# main.net
KiCad netlist of a schematic drawn in Altium Designer
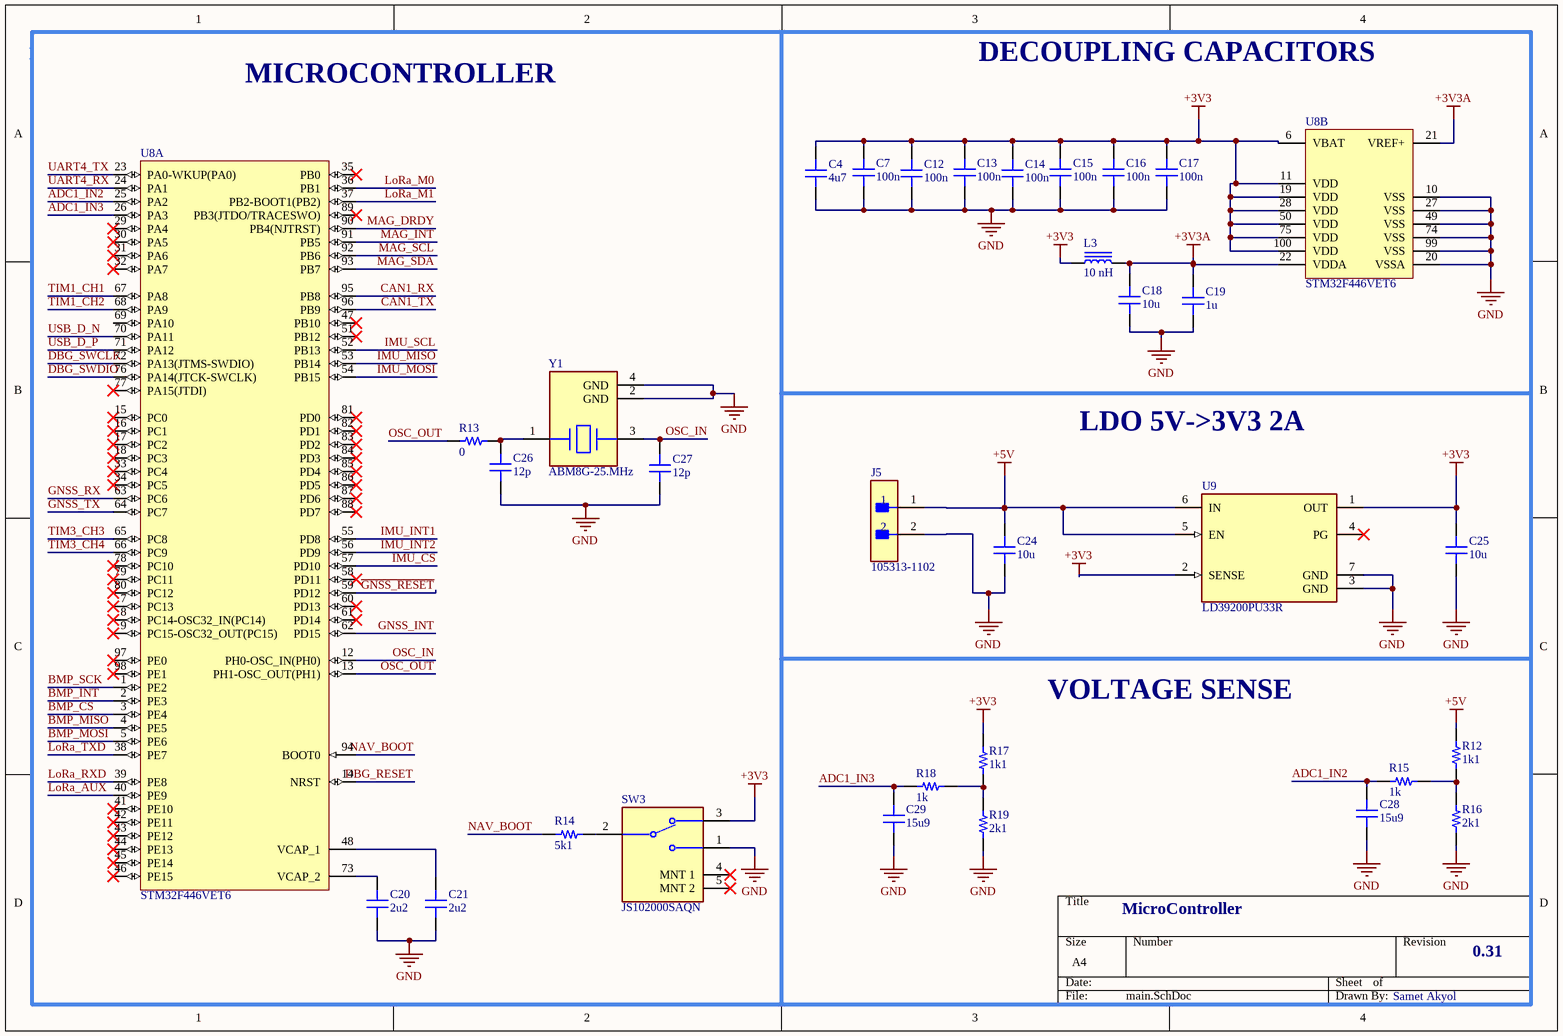
[diagram p0: main.SchDoc]

(export (version "E")
  (design (tool "Eeschema 10.0.6"))
  (components
    (comp (ref "C4")
      (value "4u7")
      (footprint "CAP 0402_1005")
      (description "CAP CER 0.1UF 10V X7R 0402")
      (fields
        (field (name "PART NUMBER") "MD0402BB104K100NGHT-EM")
        (field (name "MANUFACTURER") "Knowles Novacap")
      )
      (libsource (lib "Celestial Altium Library - altium_library") (part "Capacitor"))
    )
    (comp (ref "C7")
      (value "100n")
      (footprint "CAP 0402_1005")
      (description "CAP CER 0.1UF 10V X7R 0402")
      (fields
        (field (name "PART NUMBER") "MD0402BB104K100NGHT-EM")
        (field (name "MANUFACTURER") "Knowles Novacap")
      )
      (libsource (lib "Celestial Altium Library - altium_library") (part "Capacitor"))
    )
    (comp (ref "C12")
      (value "100n")
      (footprint "CAP 0402_1005")
      (description "CAP CER 0.1UF 10V X7R 0402")
      (fields
        (field (name "PART NUMBER") "MD0402BB104K100NGHT-EM")
        (field (name "MANUFACTURER") "Knowles Novacap")
      )
      (libsource (lib "Celestial Altium Library - altium_library") (part "Capacitor"))
    )
    (comp (ref "C13")
      (value "100n")
      (footprint "CAP 0402_1005")
      (description "CAP CER 0.1UF 10V X7R 0402")
      (fields
        (field (name "PART NUMBER") "MD0402BB104K100NGHT-EM")
        (field (name "MANUFACTURER") "Knowles Novacap")
      )
      (libsource (lib "Celestial Altium Library - altium_library") (part "Capacitor"))
    )
    (comp (ref "C14")
      (value "100n")
      (footprint "CAP 0402_1005")
      (description "CAP CER 0.1UF 10V X7R 0402")
      (fields
        (field (name "PART NUMBER") "MD0402BB104K100NGHT-EM")
        (field (name "MANUFACTURER") "Knowles Novacap")
      )
      (libsource (lib "Celestial Altium Library - altium_library") (part "Capacitor"))
    )
    (comp (ref "C15")
      (value "100n")
      (footprint "CAP 0402_1005")
      (description "CAP CER 0.1UF 10V X7R 0402")
      (fields
        (field (name "PART NUMBER") "MD0402BB104K100NGHT-EM")
        (field (name "MANUFACTURER") "Knowles Novacap")
      )
      (libsource (lib "Celestial Altium Library - altium_library") (part "Capacitor"))
    )
    (comp (ref "C16")
      (value "100n")
      (footprint "CAP 0402_1005")
      (description "CAP CER 0.1UF 10V X7R 0402")
      (fields
        (field (name "PART NUMBER") "MD0402BB104K100NGHT-EM")
        (field (name "MANUFACTURER") "Knowles Novacap")
      )
      (libsource (lib "Celestial Altium Library - altium_library") (part "Capacitor"))
    )
    (comp (ref "C17")
      (value "100n")
      (footprint "CAP 0402_1005")
      (description "CAP CER 0.1UF 10V X7R 0402")
      (fields
        (field (name "PART NUMBER") "MD0402BB104K100NGHT-EM")
        (field (name "MANUFACTURER") "Knowles Novacap")
      )
      (libsource (lib "Celestial Altium Library - altium_library") (part "Capacitor"))
    )
    (comp (ref "C18")
      (value "10u")
      (footprint "CAP 0402_1005")
      (description "CAP CER 0.1UF 10V X7R 0402")
      (fields
        (field (name "PART NUMBER") "MD0402BB104K100NGHT-EM")
        (field (name "MANUFACTURER") "Knowles Novacap")
      )
      (libsource (lib "Celestial Altium Library - altium_library") (part "Capacitor"))
    )
    (comp (ref "C19")
      (value "1u")
      (footprint "CAP 0402_1005")
      (description "CAP CER 0.1UF 10V X7R 0402")
      (fields
        (field (name "PART NUMBER") "MD0402BB104K100NGHT-EM")
        (field (name "MANUFACTURER") "Knowles Novacap")
      )
      (libsource (lib "Celestial Altium Library - altium_library") (part "Capacitor"))
    )
    (comp (ref "C20")
      (value "2u2")
      (footprint "CAP 0402_1005")
      (description "CAP CER 0.1UF 10V X7R 0402")
      (fields
        (field (name "PART NUMBER") "MD0402BB104K100NGHT-EM")
        (field (name "MANUFACTURER") "Knowles Novacap")
      )
      (libsource (lib "Celestial Altium Library - altium_library") (part "Capacitor"))
    )
    (comp (ref "C21")
      (value "2u2")
      (footprint "CAP 0402_1005")
      (description "CAP CER 0.1UF 10V X7R 0402")
      (fields
        (field (name "PART NUMBER") "MD0402BB104K100NGHT-EM")
        (field (name "MANUFACTURER") "Knowles Novacap")
      )
      (libsource (lib "Celestial Altium Library - altium_library") (part "Capacitor"))
    )
    (comp (ref "C24")
      (value "10u")
      (footprint "CAP 0603_1608")
      (description "CAP CER 3600PF 50V C0G/NP0 0603")
      (fields
        (field (name "PART NUMBER") "GRM1885C1H362JA01D")
        (field (name "MANUFACTURER") "Murata Electronics")
      )
      (libsource (lib "Celestial Altium Library - altium_library") (part "Capacitor"))
    )
    (comp (ref "C25")
      (value "10u")
      (footprint "CAP 0603_1608")
      (description "CAP CER 3600PF 50V C0G/NP0 0603")
      (fields
        (field (name "PART NUMBER") "GRM1885C1H362JA01D")
        (field (name "MANUFACTURER") "Murata Electronics")
      )
      (libsource (lib "Celestial Altium Library - altium_library") (part "Capacitor"))
    )
    (comp (ref "C26")
      (value "12p")
      (footprint "CAP 0402_1005")
      (description "CAP CER 0.1UF 10V X7R 0402")
      (fields
        (field (name "PART NUMBER") "MD0402BB104K100NGHT-EM")
        (field (name "MANUFACTURER") "Knowles Novacap")
      )
      (libsource (lib "Celestial Altium Library - altium_library") (part "Capacitor"))
    )
    (comp (ref "C27")
      (value "12p")
      (footprint "CAP 0402_1005")
      (description "CAP CER 0.1UF 10V X7R 0402")
      (fields
        (field (name "PART NUMBER") "MD0402BB104K100NGHT-EM")
        (field (name "MANUFACTURER") "Knowles Novacap")
      )
      (libsource (lib "Celestial Altium Library - altium_library") (part "Capacitor"))
    )
    (comp (ref "C28")
      (value "15u9")
      (footprint "CAP 0402_1005")
      (description "CAP CER 0.1UF 10V X7R 0402")
      (fields
        (field (name "PART NUMBER") "MD0402BB104K100NGHT-EM")
        (field (name "MANUFACTURER") "Knowles Novacap")
      )
      (libsource (lib "Celestial Altium Library - altium_library") (part "Capacitor"))
    )
    (comp (ref "C29")
      (value "15u9")
      (footprint "CAP 0402_1005")
      (description "CAP CER 0.1UF 10V X7R 0402")
      (fields
        (field (name "PART NUMBER") "MD0402BB104K100NGHT-EM")
        (field (name "MANUFACTURER") "Knowles Novacap")
      )
      (libsource (lib "Celestial Altium Library - altium_library") (part "Capacitor"))
    )
    (comp (ref "J5")
      (value "105313-1102")
      (footprint "FP-105313-1102-MFG")
      (description "CONN HEADER R/A 2POS 2.5MM")
      (libsource (lib "Altium Content Vault") (part "3bc925449376181038e59eaffc5286c"))
    )
    (comp (ref "L3")
      (value "10 nH")
      (footprint "IND 0402_1005 RF WW")
      (description "FIXED IND 10NH 1.4A 0.081OHM SMD")
      (fields
        (field (name "PART NUMBER") "LQW15AN10NG80D")
        (field (name "MANUFACTURER") "Murata Electronics")
      )
      (libsource (lib "Celestial Altium Library - altium_library") (part "Inductor"))
    )
    (comp (ref "R12")
      (value "1k1")
      (footprint "RES 0402_1005")
      (description "RES 249K OHM 0.1% 1/10W 0402")
      (fields
        (field (name "PART NUMBER") "RP73PF1E249KBTD")
        (field (name "MANUFACTURER") "TE Connectivity Passive Product")
      )
      (libsource (lib "Celestial Altium Library - altium_library") (part "Resistor"))
    )
    (comp (ref "R13")
      (value "0")
      (footprint "RES 0402_1005")
      (description "RES 270 OHM 1% 1/16W 0402")
      (fields (field (name "PART NUMBER") "RC0402FR-07270RL") (field (name "MANUFACTURER") "Yageo"))
      (libsource (lib "Celestial Altium Library - altium_library") (part "Resistor"))
    )
    (comp (ref "R14")
      (value "5k1")
      (footprint "RES 0402_1005")
      (description "RES 249K OHM 0.1% 1/10W 0402")
      (fields
        (field (name "PART NUMBER") "RP73PF1E249KBTD")
        (field (name "MANUFACTURER") "TE Connectivity Passive Product")
      )
      (libsource (lib "Celestial Altium Library - altium_library") (part "Resistor"))
    )
    (comp (ref "R15")
      (value "1k")
      (footprint "RES 0402_1005")
      (description "RES 249K OHM 0.1% 1/10W 0402")
      (fields
        (field (name "PART NUMBER") "RP73PF1E249KBTD")
        (field (name "MANUFACTURER") "TE Connectivity Passive Product")
      )
      (libsource (lib "Celestial Altium Library - altium_library") (part "Resistor"))
    )
    (comp (ref "R16")
      (value "2k1")
      (footprint "RES 0402_1005")
      (description "RES 249K OHM 0.1% 1/10W 0402")
      (fields
        (field (name "PART NUMBER") "RP73PF1E249KBTD")
        (field (name "MANUFACTURER") "TE Connectivity Passive Product")
      )
      (libsource (lib "Celestial Altium Library - altium_library") (part "Resistor"))
    )
    (comp (ref "R17")
      (value "1k1")
      (footprint "RES 0402_1005")
      (description "RES 249K OHM 0.1% 1/10W 0402")
      (fields
        (field (name "PART NUMBER") "RP73PF1E249KBTD")
        (field (name "MANUFACTURER") "TE Connectivity Passive Product")
      )
      (libsource (lib "Celestial Altium Library - altium_library") (part "Resistor"))
    )
    (comp (ref "R18")
      (value "1k")
      (footprint "RES 0402_1005")
      (description "RES 249K OHM 0.1% 1/10W 0402")
      (fields
        (field (name "PART NUMBER") "RP73PF1E249KBTD")
        (field (name "MANUFACTURER") "TE Connectivity Passive Product")
      )
      (libsource (lib "Celestial Altium Library - altium_library") (part "Resistor"))
    )
    (comp (ref "R19")
      (value "2k1")
      (footprint "RES 0402_1005")
      (description "RES 249K OHM 0.1% 1/10W 0402")
      (fields
        (field (name "PART NUMBER") "RP73PF1E249KBTD")
        (field (name "MANUFACTURER") "TE Connectivity Passive Product")
      )
      (libsource (lib "Celestial Altium Library - altium_library") (part "Resistor"))
    )
    (comp (ref "SW3")
      (value "JS102000SAQN")
      (footprint "FP-JS102000SAQN-MFG")
      (description "SWITCH SLIDE SPDT 1MA 5V")
      (libsource (lib "Altium Content Vault") (part "6887e5fe807d9c5c2853bed39bc55bf"))
    )
    (comp (ref "U8")
      (value "STM32F446VET6")
      (footprint "STM-LQFP100_L")
      (libsource (lib "Altium Content Vault") (part "MC-ARM-STM32F446-LQFP100"))
    )
    (comp (ref "U9")
      (value "LD39200PU33R")
      (footprint "FP-DFN6-7946637-MFG")
      (description "IC REG LINEAR 3.3V 2A 6DFN")
      (libsource (lib "Altium Content Vault") (part "f0cfe00d12cb984572f50007c934a2d"))
    )
    (comp (ref "Y1")
      (value "ABM8G-25.MHz")
      (footprint "FP-ABM8G-MFG")
      (description "Crystal 25MHz ±20ppm (Tol) ±30ppm (Stability) 18pF FUND 60Ω 4-Pin SMD T/R")
      (fields (field (name "TOLERANCE") "20ppm"))
      (libsource (lib "Altium Content Vault") (part "48e526d86b7f2615d98721063c72f49"))
    )
  )
  (nets
    (net (code "1") (name "+3V3") (class "Default")
      (node (ref "C12") (pin "2") (pinfunction "2_2") (pintype "passive"))
      (node (ref "C13") (pin "2") (pinfunction "2_2") (pintype "passive"))
      (node (ref "C14") (pin "2") (pinfunction "2_2") (pintype "passive"))
      (node (ref "C15") (pin "2") (pinfunction "2_2") (pintype "passive"))
      (node (ref "C16") (pin "2") (pinfunction "2_2") (pintype "passive"))
      (node (ref "C17") (pin "2") (pinfunction "2_2") (pintype "passive"))
      (node (ref "C25") (pin "2") (pinfunction "2_2") (pintype "passive"))
      (node (ref "C4") (pin "2") (pinfunction "2_2") (pintype "passive"))
      (node (ref "C7") (pin "2") (pinfunction "2_2") (pintype "passive"))
      (node (ref "L3") (pin "1") (pinfunction "1_1") (pintype "passive"))
      (node (ref "R17") (pin "2") (pinfunction "2_2") (pintype "passive"))
      (node (ref "SW3") (pin "3") (pinfunction "3_3") (pintype "passive"))
      (node (ref "U8") (pin "100") (pinfunction "VDD_100") (pintype "power_in"))
      (node (ref "U8") (pin "11") (pinfunction "VDD_11") (pintype "power_in"))
      (node (ref "U8") (pin "19") (pinfunction "VDD_19") (pintype "power_in"))
      (node (ref "U8") (pin "28") (pinfunction "VDD_28") (pintype "power_in"))
      (node (ref "U8") (pin "50") (pinfunction "VDD_50") (pintype "power_in"))
      (node (ref "U8") (pin "6") (pinfunction "VBAT_6") (pintype "power_in"))
      (node (ref "U8") (pin "75") (pinfunction "VDD_75") (pintype "power_in"))
      (node (ref "U9") (pin "1") (pinfunction "OUT_1") (pintype "power_in"))
      (node (ref "U9") (pin "2") (pinfunction "SENSE_2") (pintype "input"))
    )
    (net (code "2") (name "+3V3A") (class "Default")
      (node (ref "C18") (pin "2") (pinfunction "2_2") (pintype "passive"))
      (node (ref "C19") (pin "2") (pinfunction "2_2") (pintype "passive"))
      (node (ref "L3") (pin "2") (pinfunction "2_2") (pintype "passive"))
      (node (ref "U8") (pin "21") (pinfunction "VREF+_21") (pintype "power_in"))
      (node (ref "U8") (pin "22") (pinfunction "VDDA_22") (pintype "power_in"))
    )
    (net (code "3") (name "+5V") (class "Default")
      (node (ref "C24") (pin "2") (pinfunction "2_2") (pintype "passive"))
      (node (ref "J5") (pin "1") (pinfunction "1_1") (pintype "passive"))
      (node (ref "R12") (pin "2") (pinfunction "2_2") (pintype "passive"))
      (node (ref "U9") (pin "5") (pinfunction "EN_5") (pintype "input"))
      (node (ref "U9") (pin "6") (pinfunction "IN_6") (pintype "power_in"))
    )
    (net (code "4") (name "/ADC1_IN2") (class "Default")
      (node (ref "C28") (pin "2") (pinfunction "2_2") (pintype "passive"))
      (node (ref "R15") (pin "2") (pinfunction "2_2") (pintype "passive"))
      (node (ref "U8") (pin "25") (pinfunction "PA2_25") (pintype "bidirectional"))
    )
    (net (code "5") (name "/ADC1_IN3") (class "Default")
      (node (ref "C29") (pin "2") (pinfunction "2_2") (pintype "passive"))
      (node (ref "R18") (pin "2") (pinfunction "2_2") (pintype "passive"))
      (node (ref "U8") (pin "26") (pinfunction "PA3_26") (pintype "bidirectional"))
    )
    (net (code "6") (name "/BMP_CS") (class "Default")
      (node (ref "U8") (pin "3") (pinfunction "PE4_3") (pintype "bidirectional"))
    )
    (net (code "7") (name "/BMP_INT") (class "Default")
      (node (ref "U8") (pin "2") (pinfunction "PE3_2") (pintype "bidirectional"))
    )
    (net (code "8") (name "/BMP_MISO") (class "Default")
      (node (ref "U8") (pin "4") (pinfunction "PE5_4") (pintype "bidirectional"))
    )
    (net (code "9") (name "/BMP_MOSI") (class "Default")
      (node (ref "U8") (pin "5") (pinfunction "PE6_5") (pintype "bidirectional"))
    )
    (net (code "10") (name "/BMP_SCK") (class "Default")
      (node (ref "U8") (pin "1") (pinfunction "PE2_1") (pintype "bidirectional"))
    )
    (net (code "11") (name "/CAN1_RX") (class "Default")
      (node (ref "U8") (pin "95") (pinfunction "PB8_95") (pintype "bidirectional"))
    )
    (net (code "12") (name "/CAN1_TX") (class "Default")
      (node (ref "U8") (pin "96") (pinfunction "PB9_96") (pintype "bidirectional"))
    )
    (net (code "13") (name "/DBG_RESET") (class "Default")
      (node (ref "U8") (pin "14") (pinfunction "NRST_14") (pintype "bidirectional"))
    )
    (net (code "14") (name "/DBG_SWCLK") (class "Default")
      (node (ref "U8") (pin "72") (pinfunction "PA13(JTMS-SWDIO)_72") (pintype "bidirectional"))
    )
    (net (code "15") (name "/DBG_SWDIO") (class "Default")
      (node (ref "U8") (pin "76") (pinfunction "PA14(JTCK-SWCLK)_76") (pintype "bidirectional"))
    )
    (net (code "16") (name "/GNSS_INT") (class "Default")
      (node (ref "U8") (pin "62") (pinfunction "PD15_62") (pintype "bidirectional"))
    )
    (net (code "17") (name "/GNSS_RX") (class "Default")
      (node (ref "U8") (pin "63") (pinfunction "PC6_63") (pintype "bidirectional"))
    )
    (net (code "18") (name "/GNSS_TX") (class "Default")
      (node (ref "U8") (pin "64") (pinfunction "PC7_64") (pintype "bidirectional"))
    )
    (net (code "19") (name "/IMU_CS") (class "Default")
      (node (ref "U8") (pin "57") (pinfunction "PD10_57") (pintype "bidirectional"))
    )
    (net (code "20") (name "/IMU_INT1") (class "Default")
      (node (ref "U8") (pin "55") (pinfunction "PD8_55") (pintype "bidirectional"))
    )
    (net (code "21") (name "/IMU_INT2") (class "Default")
      (node (ref "U8") (pin "56") (pinfunction "PD9_56") (pintype "bidirectional"))
    )
    (net (code "22") (name "/IMU_MISO") (class "Default")
      (node (ref "U8") (pin "53") (pinfunction "PB14_53") (pintype "bidirectional"))
    )
    (net (code "23") (name "/IMU_MOSI") (class "Default")
      (node (ref "U8") (pin "54") (pinfunction "PB15_54") (pintype "bidirectional"))
    )
    (net (code "24") (name "/IMU_SCL") (class "Default")
      (node (ref "U8") (pin "52") (pinfunction "PB13_52") (pintype "bidirectional"))
    )
    (net (code "25") (name "/LoRa_AUX") (class "Default")
      (node (ref "U8") (pin "40") (pinfunction "PE9_40") (pintype "bidirectional"))
    )
    (net (code "26") (name "/LoRa_M0") (class "Default")
      (node (ref "U8") (pin "36") (pinfunction "PB1_36") (pintype "bidirectional"))
    )
    (net (code "27") (name "/LoRa_M1") (class "Default")
      (node (ref "U8") (pin "37") (pinfunction "PB2-BOOT1(PB2)_37") (pintype "bidirectional"))
    )
    (net (code "28") (name "/LoRa_RXD") (class "Default")
      (node (ref "U8") (pin "39") (pinfunction "PE8_39") (pintype "bidirectional"))
    )
    (net (code "29") (name "/LoRa_TXD") (class "Default")
      (node (ref "U8") (pin "38") (pinfunction "PE7_38") (pintype "bidirectional"))
    )
    (net (code "30") (name "/MAG_DRDY") (class "Default")
      (node (ref "U8") (pin "90") (pinfunction "PB4(NJTRST)_90") (pintype "bidirectional"))
    )
    (net (code "31") (name "/MAG_INT") (class "Default")
      (node (ref "U8") (pin "91") (pinfunction "PB5_91") (pintype "bidirectional"))
    )
    (net (code "32") (name "/MAG_SCL") (class "Default")
      (node (ref "U8") (pin "92") (pinfunction "PB6_92") (pintype "bidirectional"))
    )
    (net (code "33") (name "/MAG_SDA") (class "Default")
      (node (ref "U8") (pin "93") (pinfunction "PB7_93") (pintype "bidirectional"))
    )
    (net (code "34") (name "/NAV_BOOT") (class "Default")
      (node (ref "R14") (pin "2") (pinfunction "2_2") (pintype "passive"))
      (node (ref "U8") (pin "94") (pinfunction "BOOT0_94") (pintype "input"))
    )
    (net (code "35") (name "/OSC_IN") (class "Default")
      (node (ref "C27") (pin "2") (pinfunction "2_2") (pintype "passive"))
      (node (ref "U8") (pin "12") (pinfunction "PH0-OSC_IN(PH0)_12") (pintype "bidirectional"))
      (node (ref "Y1") (pin "3") (pinfunction "3_3") (pintype "passive"))
    )
    (net (code "36") (name "/OSC_OUT") (class "Default")
      (node (ref "R13") (pin "1") (pinfunction "1_1") (pintype "passive"))
      (node (ref "U8") (pin "13") (pinfunction "PH1-OSC_OUT(PH1)_13") (pintype "bidirectional"))
    )
    (net (code "37") (name "/TIM1_CH1") (class "Default")
      (node (ref "U8") (pin "67") (pinfunction "PA8_67") (pintype "bidirectional"))
    )
    (net (code "38") (name "/TIM1_CH2") (class "Default")
      (node (ref "U8") (pin "68") (pinfunction "PA9_68") (pintype "bidirectional"))
    )
    (net (code "39") (name "/TIM3_CH3") (class "Default")
      (node (ref "U8") (pin "65") (pinfunction "PC8_65") (pintype "bidirectional"))
    )
    (net (code "40") (name "/TIM3_CH4") (class "Default")
      (node (ref "U8") (pin "66") (pinfunction "PC9_66") (pintype "bidirectional"))
    )
    (net (code "41") (name "/UART4_RX") (class "Default")
      (node (ref "U8") (pin "24") (pinfunction "PA1_24") (pintype "bidirectional"))
    )
    (net (code "42") (name "/UART4_TX") (class "Default")
      (node (ref "U8") (pin "23") (pinfunction "PA0-WKUP(PA0)_23") (pintype "bidirectional"))
    )
    (net (code "43") (name "/USB_D_N") (class "Default")
      (node (ref "U8") (pin "70") (pinfunction "PA11_70") (pintype "bidirectional"))
    )
    (net (code "44") (name "/USB_D_P") (class "Default")
      (node (ref "U8") (pin "71") (pinfunction "PA12_71") (pintype "bidirectional"))
    )
    (net (code "45") (name "/~{GNSS_RESET}") (class "Default")
      (node (ref "U8") (pin "59") (pinfunction "PD12_59") (pintype "bidirectional"))
    )
    (net (code "46") (name "GND") (class "Default")
      (node (ref "C12") (pin "1") (pinfunction "1_1") (pintype "passive"))
      (node (ref "C13") (pin "1") (pinfunction "1_1") (pintype "passive"))
      (node (ref "C14") (pin "1") (pinfunction "1_1") (pintype "passive"))
      (node (ref "C15") (pin "1") (pinfunction "1_1") (pintype "passive"))
      (node (ref "C16") (pin "1") (pinfunction "1_1") (pintype "passive"))
      (node (ref "C17") (pin "1") (pinfunction "1_1") (pintype "passive"))
      (node (ref "C18") (pin "1") (pinfunction "1_1") (pintype "passive"))
      (node (ref "C19") (pin "1") (pinfunction "1_1") (pintype "passive"))
      (node (ref "C20") (pin "1") (pinfunction "1_1") (pintype "passive"))
      (node (ref "C21") (pin "1") (pinfunction "1_1") (pintype "passive"))
      (node (ref "C24") (pin "1") (pinfunction "1_1") (pintype "passive"))
      (node (ref "C25") (pin "1") (pinfunction "1_1") (pintype "passive"))
      (node (ref "C26") (pin "1") (pinfunction "1_1") (pintype "passive"))
      (node (ref "C27") (pin "1") (pinfunction "1_1") (pintype "passive"))
      (node (ref "C28") (pin "1") (pinfunction "1_1") (pintype "passive"))
      (node (ref "C29") (pin "1") (pinfunction "1_1") (pintype "passive"))
      (node (ref "C4") (pin "1") (pinfunction "1_1") (pintype "passive"))
      (node (ref "C7") (pin "1") (pinfunction "1_1") (pintype "passive"))
      (node (ref "J5") (pin "2") (pinfunction "2_2") (pintype "passive"))
      (node (ref "R16") (pin "2") (pinfunction "2_2") (pintype "passive"))
      (node (ref "R19") (pin "2") (pinfunction "2_2") (pintype "passive"))
      (node (ref "SW3") (pin "1") (pinfunction "1_1") (pintype "passive"))
      (node (ref "U8") (pin "10") (pinfunction "VSS_10") (pintype "power_in"))
      (node (ref "U8") (pin "20") (pinfunction "VSSA_20") (pintype "power_in"))
      (node (ref "U8") (pin "27") (pinfunction "VSS_27") (pintype "power_in"))
      (node (ref "U8") (pin "49") (pinfunction "VSS_49") (pintype "power_in"))
      (node (ref "U8") (pin "74") (pinfunction "VSS_74") (pintype "power_in"))
      (node (ref "U8") (pin "99") (pinfunction "VSS_99") (pintype "power_in"))
      (node (ref "U9") (pin "3") (pinfunction "GND_3") (pintype "power_in"))
      (node (ref "U9") (pin "7") (pinfunction "GND_7") (pintype "power_in"))
      (node (ref "Y1") (pin "2") (pinfunction "GND_2") (pintype "power_in"))
      (node (ref "Y1") (pin "4") (pinfunction "GND_4") (pintype "power_in"))
    )
    (net (code "47") (name "Net-(C26-Pad2)") (class "Default")
      (node (ref "C26") (pin "2") (pinfunction "2_2") (pintype "passive"))
      (node (ref "R13") (pin "2") (pinfunction "2_2") (pintype "passive"))
      (node (ref "Y1") (pin "1") (pinfunction "1_1") (pintype "passive"))
    )
    (net (code "48") (name "Net-(R12-Pad1)") (class "Default")
      (node (ref "R12") (pin "1") (pinfunction "1_1") (pintype "passive"))
      (node (ref "R15") (pin "1") (pinfunction "1_1") (pintype "passive"))
      (node (ref "R16") (pin "1") (pinfunction "1_1") (pintype "passive"))
    )
    (net (code "49") (name "Net-(R17-Pad1)") (class "Default")
      (node (ref "R17") (pin "1") (pinfunction "1_1") (pintype "passive"))
      (node (ref "R18") (pin "1") (pinfunction "1_1") (pintype "passive"))
      (node (ref "R19") (pin "1") (pinfunction "1_1") (pintype "passive"))
    )
    (net (code "50") (name "Net-(SW3-C)") (class "Default")
      (node (ref "R14") (pin "1") (pinfunction "1_1") (pintype "passive"))
      (node (ref "SW3") (pin "2") (pinfunction "C_2") (pintype "passive"))
    )
    (net (code "51") (name "Net-(U8A-VCAP_1)") (class "Default")
      (node (ref "C21") (pin "2") (pinfunction "2_2") (pintype "passive"))
      (node (ref "U8") (pin "48") (pinfunction "VCAP_1_48") (pintype "passive"))
    )
    (net (code "52") (name "Net-(U8A-VCAP_2)") (class "Default")
      (node (ref "C20") (pin "2") (pinfunction "2_2") (pintype "passive"))
      (node (ref "U8") (pin "73") (pinfunction "VCAP_2_73") (pintype "passive"))
    )
    (net (code "53") (name "unconnected-(SW3-MNT_1-Pad4)") (class "Default")
      (node (ref "SW3") (pin "4") (pinfunction "MNT_1_4") (pintype "passive+no_connect"))
    )
    (net (code "54") (name "unconnected-(SW3-MNT_2-Pad5)") (class "Default")
      (node (ref "SW3") (pin "5") (pinfunction "MNT_2_5") (pintype "passive+no_connect"))
    )
    (net (code "55") (name "unconnected-(U8A-PA4-Pad29)") (class "Default")
      (node (ref "U8") (pin "29") (pinfunction "PA4_29") (pintype "bidirectional+no_connect"))
    )
    (net (code "56") (name "unconnected-(U8A-PA5-Pad30)") (class "Default")
      (node (ref "U8") (pin "30") (pinfunction "PA5_30") (pintype "bidirectional+no_connect"))
    )
    (net (code "57") (name "unconnected-(U8A-PA6-Pad31)") (class "Default")
      (node (ref "U8") (pin "31") (pinfunction "PA6_31") (pintype "bidirectional+no_connect"))
    )
    (net (code "58") (name "unconnected-(U8A-PA7-Pad32)") (class "Default")
      (node (ref "U8") (pin "32") (pinfunction "PA7_32") (pintype "bidirectional+no_connect"))
    )
    (net (code "59") (name "unconnected-(U8A-PA10-Pad69)") (class "Default")
      (node (ref "U8") (pin "69") (pinfunction "PA10_69") (pintype "bidirectional"))
    )
    (net (code "60") (name "unconnected-(U8A-PA15(JTDI)-Pad77)") (class "Default")
      (node (ref "U8") (pin "77") (pinfunction "PA15(JTDI)_77") (pintype "bidirectional+no_connect"))
    )
    (net (code "61") (name "unconnected-(U8A-PB0-Pad35)") (class "Default")
      (node (ref "U8") (pin "35") (pinfunction "PB0_35") (pintype "bidirectional+no_connect"))
    )
    (net (code "62") (name "unconnected-(U8A-PB3(JTDO{slash}TRACESWO)-Pad89)") (class "Default")
      (node (ref "U8") (pin "89") (pinfunction "PB3(JTDO/TRACESWO)_89") (pintype "bidirectional+no_connect"))
    )
    (net (code "63") (name "unconnected-(U8A-PB10-Pad47)") (class "Default")
      (node (ref "U8") (pin "47") (pinfunction "PB10_47") (pintype "bidirectional+no_connect"))
    )
    (net (code "64") (name "unconnected-(U8A-PB12-Pad51)") (class "Default")
      (node (ref "U8") (pin "51") (pinfunction "PB12_51") (pintype "bidirectional+no_connect"))
    )
    (net (code "65") (name "unconnected-(U8A-PC0-Pad15)") (class "Default")
      (node (ref "U8") (pin "15") (pinfunction "PC0_15") (pintype "bidirectional+no_connect"))
    )
    (net (code "66") (name "unconnected-(U8A-PC1-Pad16)") (class "Default")
      (node (ref "U8") (pin "16") (pinfunction "PC1_16") (pintype "bidirectional+no_connect"))
    )
    (net (code "67") (name "unconnected-(U8A-PC2-Pad17)") (class "Default")
      (node (ref "U8") (pin "17") (pinfunction "PC2_17") (pintype "bidirectional+no_connect"))
    )
    (net (code "68") (name "unconnected-(U8A-PC3-Pad18)") (class "Default")
      (node (ref "U8") (pin "18") (pinfunction "PC3_18") (pintype "bidirectional+no_connect"))
    )
    (net (code "69") (name "unconnected-(U8A-PC4-Pad33)") (class "Default")
      (node (ref "U8") (pin "33") (pinfunction "PC4_33") (pintype "bidirectional+no_connect"))
    )
    (net (code "70") (name "unconnected-(U8A-PC5-Pad34)") (class "Default")
      (node (ref "U8") (pin "34") (pinfunction "PC5_34") (pintype "bidirectional+no_connect"))
    )
    (net (code "71") (name "unconnected-(U8A-PC10-Pad78)") (class "Default")
      (node (ref "U8") (pin "78") (pinfunction "PC10_78") (pintype "bidirectional+no_connect"))
    )
    (net (code "72") (name "unconnected-(U8A-PC11-Pad79)") (class "Default")
      (node (ref "U8") (pin "79") (pinfunction "PC11_79") (pintype "bidirectional+no_connect"))
    )
    (net (code "73") (name "unconnected-(U8A-PC12-Pad80)") (class "Default")
      (node (ref "U8") (pin "80") (pinfunction "PC12_80") (pintype "bidirectional+no_connect"))
    )
    (net (code "74") (name "unconnected-(U8A-PC13-Pad7)") (class "Default")
      (node (ref "U8") (pin "7") (pinfunction "PC13_7") (pintype "bidirectional+no_connect"))
    )
    (net (code "75") (name "unconnected-(U8A-PC14-OSC32_IN(PC14)-Pad8)") (class "Default")
      (node (ref "U8") (pin "8") (pinfunction "PC14-OSC32_IN(PC14)_8") (pintype "bidirectional+no_connect"))
    )
    (net (code "76") (name "unconnected-(U8A-PC15-OSC32_OUT(PC15)-Pad9)") (class "Default")
      (node (ref "U8") (pin "9") (pinfunction "PC15-OSC32_OUT(PC15)_9") (pintype "bidirectional+no_connect"))
    )
    (net (code "77") (name "unconnected-(U8A-PD0-Pad81)") (class "Default")
      (node (ref "U8") (pin "81") (pinfunction "PD0_81") (pintype "bidirectional+no_connect"))
    )
    (net (code "78") (name "unconnected-(U8A-PD1-Pad82)") (class "Default")
      (node (ref "U8") (pin "82") (pinfunction "PD1_82") (pintype "bidirectional+no_connect"))
    )
    (net (code "79") (name "unconnected-(U8A-PD2-Pad83)") (class "Default")
      (node (ref "U8") (pin "83") (pinfunction "PD2_83") (pintype "bidirectional+no_connect"))
    )
    (net (code "80") (name "unconnected-(U8A-PD3-Pad84)") (class "Default")
      (node (ref "U8") (pin "84") (pinfunction "PD3_84") (pintype "bidirectional+no_connect"))
    )
    (net (code "81") (name "unconnected-(U8A-PD4-Pad85)") (class "Default")
      (node (ref "U8") (pin "85") (pinfunction "PD4_85") (pintype "bidirectional+no_connect"))
    )
    (net (code "82") (name "unconnected-(U8A-PD5-Pad86)") (class "Default")
      (node (ref "U8") (pin "86") (pinfunction "PD5_86") (pintype "bidirectional+no_connect"))
    )
    (net (code "83") (name "unconnected-(U8A-PD6-Pad87)") (class "Default")
      (node (ref "U8") (pin "87") (pinfunction "PD6_87") (pintype "bidirectional+no_connect"))
    )
    (net (code "84") (name "unconnected-(U8A-PD7-Pad88)") (class "Default")
      (node (ref "U8") (pin "88") (pinfunction "PD7_88") (pintype "bidirectional+no_connect"))
    )
    (net (code "85") (name "unconnected-(U8A-PD11-Pad58)") (class "Default")
      (node (ref "U8") (pin "58") (pinfunction "PD11_58") (pintype "bidirectional+no_connect"))
    )
    (net (code "86") (name "unconnected-(U8A-PD13-Pad60)") (class "Default")
      (node (ref "U8") (pin "60") (pinfunction "PD13_60") (pintype "bidirectional+no_connect"))
    )
    (net (code "87") (name "unconnected-(U8A-PD14-Pad61)") (class "Default")
      (node (ref "U8") (pin "61") (pinfunction "PD14_61") (pintype "bidirectional+no_connect"))
    )
    (net (code "88") (name "unconnected-(U8A-PE0-Pad97)") (class "Default")
      (node (ref "U8") (pin "97") (pinfunction "PE0_97") (pintype "bidirectional+no_connect"))
    )
    (net (code "89") (name "unconnected-(U8A-PE1-Pad98)") (class "Default")
      (node (ref "U8") (pin "98") (pinfunction "PE1_98") (pintype "bidirectional+no_connect"))
    )
    (net (code "90") (name "unconnected-(U8A-PE10-Pad41)") (class "Default")
      (node (ref "U8") (pin "41") (pinfunction "PE10_41") (pintype "bidirectional+no_connect"))
    )
    (net (code "91") (name "unconnected-(U8A-PE11-Pad42)") (class "Default")
      (node (ref "U8") (pin "42") (pinfunction "PE11_42") (pintype "bidirectional+no_connect"))
    )
    (net (code "92") (name "unconnected-(U8A-PE12-Pad43)") (class "Default")
      (node (ref "U8") (pin "43") (pinfunction "PE12_43") (pintype "bidirectional+no_connect"))
    )
    (net (code "93") (name "unconnected-(U8A-PE13-Pad44)") (class "Default")
      (node (ref "U8") (pin "44") (pinfunction "PE13_44") (pintype "bidirectional+no_connect"))
    )
    (net (code "94") (name "unconnected-(U8A-PE14-Pad45)") (class "Default")
      (node (ref "U8") (pin "45") (pinfunction "PE14_45") (pintype "bidirectional+no_connect"))
    )
    (net (code "95") (name "unconnected-(U8A-PE15-Pad46)") (class "Default")
      (node (ref "U8") (pin "46") (pinfunction "PE15_46") (pintype "bidirectional+no_connect"))
    )
    (net (code "96") (name "unconnected-(U9-PG-Pad4)") (class "Default")
      (node (ref "U9") (pin "4") (pinfunction "PG_4") (pintype "open_collector+no_connect"))
    )
  )
)
